# NRV-MEM-LCD.net
KiCad netlist of a schematic drawn in Altium Designer
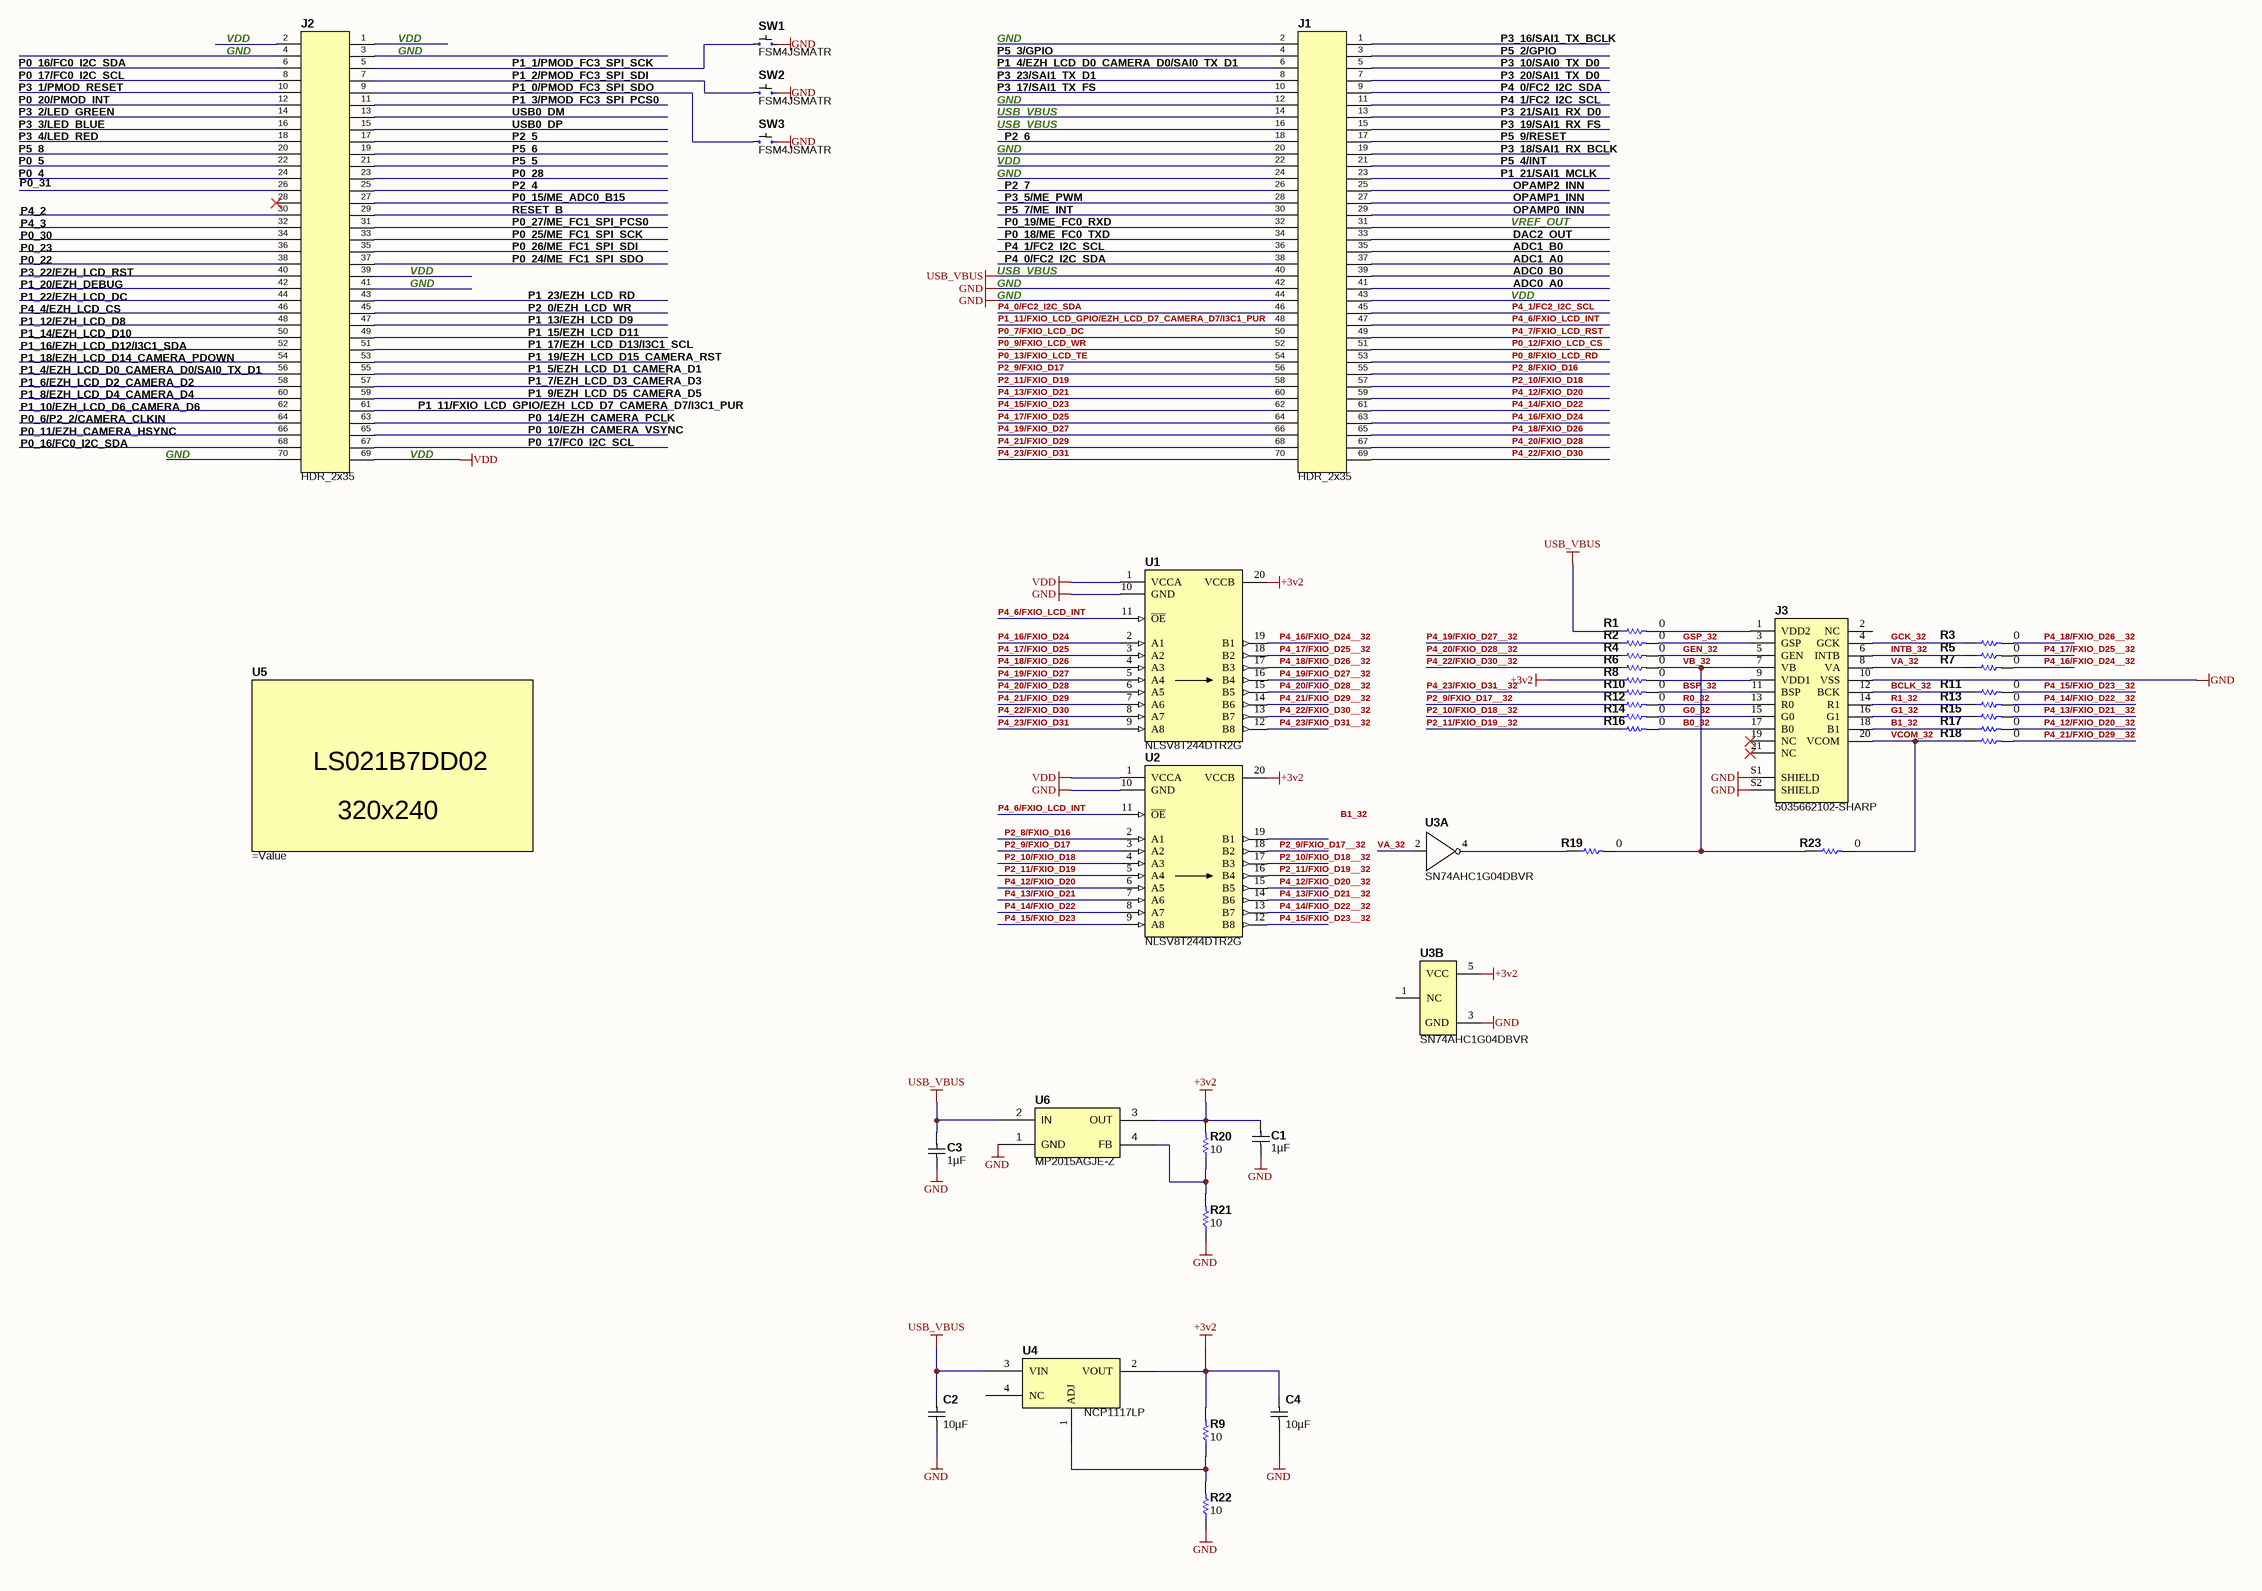
[diagram p0: NRV-MEM-LCD.SchDoc]

(export (version "E")
  (design (tool "Eeschema 10.0.6"))
  (components
    (comp (ref "C1")
      (value "1µF")
      (footprint "C0805_1.40MM_MD")
      (description "CAP CER 1UF 16V X7R 0805")
      (fields
        (field (name "MANUFACTURER PART NUMBER") "GCM21BR71C105KA58K")
        (field (name "MANUFACTURER") "Murata Electronics")
      )
      (libsource (lib "Capacitors - Murata - AEC-Q200") (part "C_2P_NP"))
    )
    (comp (ref "C2")
      (value "10µF")
      (footprint "C0805_1.40MM_MD")
      (description "CAP CER 10UF 10V X7R 0805")
      (fields
        (field (name "MANUFACTURER PART NUMBER") "GCM21BR71A106KE22K")
        (field (name "MANUFACTURER") "Murata Electronics")
      )
      (libsource (lib "Capacitors - Murata - AEC-Q200") (part "C_2P_NP"))
    )
    (comp (ref "C3")
      (value "1µF")
      (footprint "C0805_1.40MM_MD")
      (description "CAP CER 1UF 16V X7R 0805")
      (fields
        (field (name "MANUFACTURER PART NUMBER") "GCM21BR71C105KA58K")
        (field (name "MANUFACTURER") "Murata Electronics")
      )
      (libsource (lib "Capacitors - Murata - AEC-Q200") (part "C_2P_NP"))
    )
    (comp (ref "C4")
      (value "10µF")
      (footprint "C0805_1.40MM_MD")
      (description "CAP CER 10UF 10V X7R 0805")
      (fields
        (field (name "MANUFACTURER PART NUMBER") "GCM21BR71A106KE22K")
        (field (name "MANUFACTURER") "Murata Electronics")
      )
      (libsource (lib "Capacitors - Murata - AEC-Q200") (part "C_2P_NP"))
    )
    (comp (ref "J1")
      (value "HDR_2x35")
      (footprint "HEADER 2x35 .100\"")
      (description "2x35 Header .100\"")
      (libsource (lib "eConnector_Header") (part "HDR_2x35"))
    )
    (comp (ref "J2")
      (value "HDR_2x35")
      (footprint "HEADER 2x35 .100\"")
      (description "2x35 Header .100\"")
      (libsource (lib "eConnector_Header") (part "HDR_2x35"))
    )
    (comp (ref "J3")
      (value "5035662102-SHARP")
      (footprint "MOLEX_5035662102")
      (description "21 Position FPC Connector Contacts, Bottom 0.012 (0.30mm) Surface Mount, Right Angle")
      (fields (field (name "MANUFACTURER") "Molex") (field (name "MANUFACTURER PART NUMBER") "5035662102"))
      (libsource (lib "eConnector_FPC") (part "5035662102-SHARP"))
    )
    (comp (ref "R1")
      (value "0")
      (footprint "R0603_0.55MM_MD")
      (description "RES 0.0 OHM 1/10W JUMP 0603 SMD")
      (fields
        (field (name "MANUFACTURER PART NUMBER") "ERJ-3GEY0R00V")
        (field (name "MANUFACTURER") "Panasonic Electronic Components")
      )
      (libsource (lib "Resistors - Panasonic - AEC-Q200") (part "R_2P"))
    )
    (comp (ref "R2")
      (value "0")
      (footprint "R0603_0.55MM_MD")
      (description "RES 0.0 OHM 1/10W JUMP 0603 SMD")
      (fields
        (field (name "MANUFACTURER PART NUMBER") "ERJ-3GEY0R00V")
        (field (name "MANUFACTURER") "Panasonic Electronic Components")
      )
      (libsource (lib "Resistors - Panasonic - AEC-Q200") (part "R_2P"))
    )
    (comp (ref "R3")
      (value "0")
      (footprint "R0603_0.55MM_MD")
      (description "RES 0.0 OHM 1/10W JUMP 0603 SMD")
      (fields
        (field (name "MANUFACTURER PART NUMBER") "ERJ-3GEY0R00V")
        (field (name "MANUFACTURER") "Panasonic Electronic Components")
      )
      (libsource (lib "Resistors - Panasonic - AEC-Q200") (part "R_2P"))
    )
    (comp (ref "R4")
      (value "0")
      (footprint "R0603_0.55MM_MD")
      (description "RES 0.0 OHM 1/10W JUMP 0603 SMD")
      (fields
        (field (name "MANUFACTURER PART NUMBER") "ERJ-3GEY0R00V")
        (field (name "MANUFACTURER") "Panasonic Electronic Components")
      )
      (libsource (lib "Resistors - Panasonic - AEC-Q200") (part "R_2P"))
    )
    (comp (ref "R5")
      (value "0")
      (footprint "R0603_0.55MM_MD")
      (description "RES 0.0 OHM 1/10W JUMP 0603 SMD")
      (fields
        (field (name "MANUFACTURER PART NUMBER") "ERJ-3GEY0R00V")
        (field (name "MANUFACTURER") "Panasonic Electronic Components")
      )
      (libsource (lib "Resistors - Panasonic - AEC-Q200") (part "R_2P"))
    )
    (comp (ref "R6")
      (value "0")
      (footprint "R0603_0.55MM_MD")
      (description "RES 0.0 OHM 1/10W JUMP 0603 SMD")
      (fields
        (field (name "MANUFACTURER PART NUMBER") "ERJ-3GEY0R00V")
        (field (name "MANUFACTURER") "Panasonic Electronic Components")
      )
      (libsource (lib "Resistors - Panasonic - AEC-Q200") (part "R_2P"))
    )
    (comp (ref "R7")
      (value "0")
      (footprint "R0603_0.55MM_MD")
      (description "RES 0.0 OHM 1/10W JUMP 0603 SMD")
      (fields
        (field (name "MANUFACTURER PART NUMBER") "ERJ-3GEY0R00V")
        (field (name "MANUFACTURER") "Panasonic Electronic Components")
      )
      (libsource (lib "Resistors - Panasonic - AEC-Q200") (part "R_2P"))
    )
    (comp (ref "R8")
      (value "0")
      (footprint "R0603_0.55MM_MD")
      (description "RES 0.0 OHM 1/10W JUMP 0603 SMD")
      (fields
        (field (name "MANUFACTURER PART NUMBER") "ERJ-3GEY0R00V")
        (field (name "MANUFACTURER") "Panasonic Electronic Components")
      )
      (libsource (lib "Resistors - Panasonic - AEC-Q200") (part "R_2P"))
    )
    (comp (ref "R9")
      (value "10")
      (footprint "R0603_0.55MM_MD")
      (description "RES 10.0 OHM 1/10W 1% 0603 SMD")
      (libsource (lib "eResistors") (part "R"))
    )
    (comp (ref "R10")
      (value "0")
      (footprint "R0603_0.55MM_MD")
      (description "RES 0.0 OHM 1/10W JUMP 0603 SMD")
      (fields
        (field (name "MANUFACTURER PART NUMBER") "ERJ-3GEY0R00V")
        (field (name "MANUFACTURER") "Panasonic Electronic Components")
      )
      (libsource (lib "Resistors - Panasonic - AEC-Q200") (part "R_2P"))
    )
    (comp (ref "R11")
      (value "0")
      (footprint "R0603_0.55MM_MD")
      (description "RES 0.0 OHM 1/10W JUMP 0603 SMD")
      (fields
        (field (name "MANUFACTURER PART NUMBER") "ERJ-3GEY0R00V")
        (field (name "MANUFACTURER") "Panasonic Electronic Components")
      )
      (libsource (lib "Resistors - Panasonic - AEC-Q200") (part "R_2P"))
    )
    (comp (ref "R12")
      (value "0")
      (footprint "R0603_0.55MM_MD")
      (description "RES 0.0 OHM 1/10W JUMP 0603 SMD")
      (fields
        (field (name "MANUFACTURER PART NUMBER") "ERJ-3GEY0R00V")
        (field (name "MANUFACTURER") "Panasonic Electronic Components")
      )
      (libsource (lib "Resistors - Panasonic - AEC-Q200") (part "R_2P"))
    )
    (comp (ref "R13")
      (value "0")
      (footprint "R0603_0.55MM_MD")
      (description "RES 0.0 OHM 1/10W JUMP 0603 SMD")
      (fields
        (field (name "MANUFACTURER PART NUMBER") "ERJ-3GEY0R00V")
        (field (name "MANUFACTURER") "Panasonic Electronic Components")
      )
      (libsource (lib "Resistors - Panasonic - AEC-Q200") (part "R_2P"))
    )
    (comp (ref "R14")
      (value "0")
      (footprint "R0603_0.55MM_MD")
      (description "RES 0.0 OHM 1/10W JUMP 0603 SMD")
      (fields
        (field (name "MANUFACTURER PART NUMBER") "ERJ-3GEY0R00V")
        (field (name "MANUFACTURER") "Panasonic Electronic Components")
      )
      (libsource (lib "Resistors - Panasonic - AEC-Q200") (part "R_2P"))
    )
    (comp (ref "R15")
      (value "0")
      (footprint "R0603_0.55MM_MD")
      (description "RES 0.0 OHM 1/10W JUMP 0603 SMD")
      (fields
        (field (name "MANUFACTURER PART NUMBER") "ERJ-3GEY0R00V")
        (field (name "MANUFACTURER") "Panasonic Electronic Components")
      )
      (libsource (lib "Resistors - Panasonic - AEC-Q200") (part "R_2P"))
    )
    (comp (ref "R16")
      (value "0")
      (footprint "R0603_0.55MM_MD")
      (description "RES 0.0 OHM 1/10W JUMP 0603 SMD")
      (fields
        (field (name "MANUFACTURER PART NUMBER") "ERJ-3GEY0R00V")
        (field (name "MANUFACTURER") "Panasonic Electronic Components")
      )
      (libsource (lib "Resistors - Panasonic - AEC-Q200") (part "R_2P"))
    )
    (comp (ref "R17")
      (value "0")
      (footprint "R0603_0.55MM_MD")
      (description "RES 0.0 OHM 1/10W JUMP 0603 SMD")
      (fields
        (field (name "MANUFACTURER PART NUMBER") "ERJ-3GEY0R00V")
        (field (name "MANUFACTURER") "Panasonic Electronic Components")
      )
      (libsource (lib "Resistors - Panasonic - AEC-Q200") (part "R_2P"))
    )
    (comp (ref "R18")
      (value "0")
      (footprint "R0603_0.55MM_MD")
      (description "RES 0.0 OHM 1/10W JUMP 0603 SMD")
      (fields
        (field (name "MANUFACTURER PART NUMBER") "ERJ-3GEY0R00V")
        (field (name "MANUFACTURER") "Panasonic Electronic Components")
      )
      (libsource (lib "Resistors - Panasonic - AEC-Q200") (part "R_2P"))
    )
    (comp (ref "R19")
      (value "0")
      (footprint "R0603_0.55MM_MD")
      (description "RES 0.0 OHM 1/10W JUMP 0603 SMD")
      (fields
        (field (name "MANUFACTURER PART NUMBER") "ERJ-3GEY0R00V")
        (field (name "MANUFACTURER") "Panasonic Electronic Components")
      )
      (libsource (lib "Resistors - Panasonic - AEC-Q200") (part "R_2P"))
    )
    (comp (ref "R20")
      (value "10")
      (footprint "R0603_0.55MM_MD")
      (description "RES 10.0 OHM 1/10W 1% 0603 SMD")
      (libsource (lib "eResistors") (part "R"))
    )
    (comp (ref "R21")
      (value "10")
      (footprint "R0603_0.55MM_MD")
      (description "RES 10.0 OHM 1/10W 1% 0603 SMD")
      (libsource (lib "eResistors") (part "R"))
    )
    (comp (ref "R22")
      (value "10")
      (footprint "R0603_0.55MM_MD")
      (description "RES 10.0 OHM 1/10W 1% 0603 SMD")
      (libsource (lib "eResistors") (part "R"))
    )
    (comp (ref "R23")
      (value "0")
      (footprint "R0603_0.55MM_MD")
      (description "RES 0.0 OHM 1/10W JUMP 0603 SMD")
      (fields
        (field (name "MANUFACTURER PART NUMBER") "ERJ-3GEY0R00V")
        (field (name "MANUFACTURER") "Panasonic Electronic Components")
      )
      (libsource (lib "Resistors - Panasonic - AEC-Q200") (part "R_2P"))
    )
    (comp (ref "SW1")
      (value "FSM4JSMATR")
      (footprint "FSM4JSMA")
      (description "SWITCH TACTILE SPST-NO 0.05A 12V")
      (fields (field (name "MANUFACTURER") "TE Connectivity"))
      (libsource (lib "eElectroMechanical") (part "FSM4JSMATR"))
    )
    (comp (ref "SW2")
      (value "FSM4JSMATR")
      (footprint "FSM4JSMA")
      (description "SWITCH TACTILE SPST-NO 0.05A 12V")
      (fields (field (name "MANUFACTURER") "TE Connectivity"))
      (libsource (lib "eElectroMechanical") (part "FSM4JSMATR"))
    )
    (comp (ref "SW3")
      (value "FSM4JSMATR")
      (footprint "FSM4JSMA")
      (description "SWITCH TACTILE SPST-NO 0.05A 12V")
      (fields (field (name "MANUFACTURER") "TE Connectivity"))
      (libsource (lib "eElectroMechanical") (part "FSM4JSMATR"))
    )
    (comp (ref "U1")
      (value "NLSV8T244DTR2G")
      (footprint "TSOP65P640X105-20N")
      (description "NLSV8T244 Series 8 Bit 0.9 to 4.5 V Dual Non Inverting Level Translator-TSSOP-20")
      (libsource (lib "eIC") (part "NLSV8T244DTR2G"))
    )
    (comp (ref "U2")
      (value "NLSV8T244DTR2G")
      (footprint "TSOP65P640X105-20N")
      (description "NLSV8T244 Series 8 Bit 0.9 to 4.5 V Dual Non Inverting Level Translator-TSSOP-20")
      (libsource (lib "eIC") (part "NLSV8T244DTR2G"))
    )
    (comp (ref "U3")
      (value "SN74AHC1G04DBVR")
      (footprint "SOT95P245X145-5L")
      (description "IC SINGLE INVERTER GATE SOT23-5")
      (fields (field (name "MANUFACTURER") "Texas Instruments") (field (name "SOURCE") "Digikey"))
      (libsource (lib "eIC") (part "SN74AHC1G04DBVR"))
    )
    (comp (ref "U4")
      (value "NCP1117LP")
      (footprint "SOT223")
      (description "LDO Regulator Pos 1A 4-Pin(3+Tab) SOT-223 T/R / IC REG LDO ADJ 1A SOT223")
      (fields
        (field (name "MANUFACTURER") "ON Semiconductor")
        (field (name "MANUFACTURER PART NUMBER") "NCP1117LPSTADT3G")
      )
      (libsource (lib "eIC_Regulator") (part "NCP1117LP"))
    )
    (comp (ref "U5")
      (value "~")
      (footprint "LS021B7DD02")
      (description "LCD Display Module 5.4-in 240xRGBx320 45uW")
      (fields (field (name "MANUFACTURER") "Sharp") (field (name "MANUFACTURER PART NUMBER") "LS021B7DD02"))
      (libsource (lib "eModule") (part "LS021B7DD02"))
    )
    (comp (ref "U6")
      (value "MP2015AGJE-Z")
      (footprint "SOT23-4")
      (description "LDO Voltage Regulators 24V LowQuies Current Linear Regulator")
      (fields (field (name "MANUFACTURER") "Monolithic Power Systems"))
      (libsource (lib "eIC_Regulator") (part "MP2015AGJE-Z"))
    )
  )
  (nets
    (net (code "1") (name "+3v2") (class "Default")
      (node (ref "C1") (pin "2") (pinfunction "1_2") (pintype "passive"))
      (node (ref "C4") (pin "2") (pinfunction "1_2") (pintype "passive"))
      (node (ref "R20") (pin "2") (pinfunction "2_2") (pintype "passive"))
      (node (ref "R8") (pin "1") (pinfunction "1_1") (pintype "passive"))
      (node (ref "R9") (pin "2") (pinfunction "2_2") (pintype "passive"))
      (node (ref "U1") (pin "20") (pinfunction "VCCB_20") (pintype "power_in"))
      (node (ref "U2") (pin "20") (pinfunction "VCCB_20") (pintype "power_in"))
      (node (ref "U3") (pin "5") (pinfunction "VCC_5") (pintype "passive"))
      (node (ref "U4") (pin "2") (pinfunction "VOUT_2") (pintype "passive"))
      (node (ref "U6") (pin "3") (pinfunction "OUT_3") (pintype "passive"))
    )
    (net (code "2") (name "/B0_32") (class "Default")
      (node (ref "J3") (pin "17") (pinfunction "B0_17") (pintype "passive"))
      (node (ref "R16") (pin "2") (pinfunction "2_2") (pintype "passive"))
    )
    (net (code "3") (name "/B1_32") (class "Default")
      (node (ref "J3") (pin "18") (pinfunction "B1_18") (pintype "passive"))
      (node (ref "R17") (pin "1") (pinfunction "1_1") (pintype "passive"))
    )
    (net (code "4") (name "/BCLK_32") (class "Default")
      (node (ref "J3") (pin "12") (pinfunction "BCK_12") (pintype "passive"))
      (node (ref "R11") (pin "1") (pinfunction "1_1") (pintype "passive"))
    )
    (net (code "5") (name "/BSP_32") (class "Default")
      (node (ref "J3") (pin "11") (pinfunction "BSP_11") (pintype "passive"))
      (node (ref "R10") (pin "2") (pinfunction "2_2") (pintype "passive"))
    )
    (net (code "6") (name "/G0_32") (class "Default")
      (node (ref "J3") (pin "15") (pinfunction "G0_15") (pintype "passive"))
      (node (ref "R14") (pin "2") (pinfunction "2_2") (pintype "passive"))
    )
    (net (code "7") (name "/G1_32") (class "Default")
      (node (ref "J3") (pin "16") (pinfunction "G1_16") (pintype "passive"))
      (node (ref "R15") (pin "1") (pinfunction "1_1") (pintype "passive"))
    )
    (net (code "8") (name "/GCK_32") (class "Default")
      (node (ref "J3") (pin "4") (pinfunction "GCK_4") (pintype "passive"))
      (node (ref "R3") (pin "1") (pinfunction "1_1") (pintype "passive"))
    )
    (net (code "9") (name "/GEN_32") (class "Default")
      (node (ref "J3") (pin "5") (pinfunction "GEN_5") (pintype "passive"))
      (node (ref "R4") (pin "2") (pinfunction "2_2") (pintype "passive"))
    )
    (net (code "10") (name "/GSP_32") (class "Default")
      (node (ref "J3") (pin "3") (pinfunction "GSP_3") (pintype "passive"))
      (node (ref "R2") (pin "2") (pinfunction "2_2") (pintype "passive"))
    )
    (net (code "11") (name "/INTB_32") (class "Default")
      (node (ref "J3") (pin "6") (pinfunction "INTB_6") (pintype "passive"))
      (node (ref "R5") (pin "1") (pinfunction "1_1") (pintype "passive"))
    )
    (net (code "12") (name "/P0_7{slash}FXIO_LCD_DC") (class "Default")
      (node (ref "J1") (pin "50") (pinfunction "50_50") (pintype "passive"))
    )
    (net (code "13") (name "/P0_8{slash}FXIO_LCD_RD") (class "Default")
      (node (ref "J1") (pin "53") (pinfunction "53_53") (pintype "passive"))
    )
    (net (code "14") (name "/P0_9{slash}FXIO_LCD_WR") (class "Default")
      (node (ref "J1") (pin "52") (pinfunction "52_52") (pintype "passive"))
    )
    (net (code "15") (name "/P0_12{slash}FXIO_LCD_CS") (class "Default")
      (node (ref "J1") (pin "51") (pinfunction "51_51") (pintype "passive"))
    )
    (net (code "16") (name "/P0_13{slash}FXIO_LCD_TE") (class "Default")
      (node (ref "J1") (pin "54") (pinfunction "54_54") (pintype "passive"))
    )
    (net (code "17") (name "/P1_11{slash}FXIO_LCD_GPIO{slash}EZH_LCD_D7_CAMERA_D7{slash}I3C1_PUR") (class "Default")
      (node (ref "J1") (pin "48") (pinfunction "48_48") (pintype "passive"))
    )
    (net (code "18") (name "/P2_8{slash}FXIO_D16") (class "Default")
      (node (ref "J1") (pin "55") (pinfunction "55_55") (pintype "passive"))
      (node (ref "U2") (pin "2") (pinfunction "A1_2") (pintype "input"))
    )
    (net (code "19") (name "/P2_9{slash}FXIO_D17") (class "Default")
      (node (ref "J1") (pin "56") (pinfunction "56_56") (pintype "passive"))
      (node (ref "U2") (pin "3") (pinfunction "A2_3") (pintype "input"))
    )
    (net (code "20") (name "/P2_9{slash}FXIO_D17__32") (class "Default")
      (node (ref "R12") (pin "1") (pinfunction "1_1") (pintype "passive"))
      (node (ref "U2") (pin "18") (pinfunction "B2_18") (pintype "output"))
    )
    (net (code "21") (name "/P2_10{slash}FXIO_D18") (class "Default")
      (node (ref "J1") (pin "57") (pinfunction "57_57") (pintype "passive"))
      (node (ref "U2") (pin "4") (pinfunction "A3_4") (pintype "input"))
    )
    (net (code "22") (name "/P2_10{slash}FXIO_D18__32") (class "Default")
      (node (ref "R14") (pin "1") (pinfunction "1_1") (pintype "passive"))
      (node (ref "U2") (pin "17") (pinfunction "B3_17") (pintype "output"))
    )
    (net (code "23") (name "/P2_11{slash}FXIO_D19") (class "Default")
      (node (ref "J1") (pin "58") (pinfunction "58_58") (pintype "passive"))
      (node (ref "U2") (pin "5") (pinfunction "A4_5") (pintype "input"))
    )
    (net (code "24") (name "/P2_11{slash}FXIO_D19__32") (class "Default")
      (node (ref "R16") (pin "1") (pinfunction "1_1") (pintype "passive"))
      (node (ref "U2") (pin "16") (pinfunction "B4_16") (pintype "output"))
    )
    (net (code "25") (name "/P4_0{slash}FC2_I2C_SDA") (class "Default")
      (node (ref "J1") (pin "46") (pinfunction "46_46") (pintype "passive"))
    )
    (net (code "26") (name "/P4_1{slash}FC2_I2C_SCL") (class "Default")
      (node (ref "J1") (pin "45") (pinfunction "45_45") (pintype "passive"))
    )
    (net (code "27") (name "/P4_6{slash}FXIO_LCD_INT") (class "Default")
      (node (ref "J1") (pin "47") (pinfunction "47_47") (pintype "passive"))
      (node (ref "U1") (pin "11") (pinfunction "~{OE}_11") (pintype "input"))
      (node (ref "U2") (pin "11") (pinfunction "~{OE}_11") (pintype "input"))
    )
    (net (code "28") (name "/P4_7{slash}FXIO_LCD_RST") (class "Default")
      (node (ref "J1") (pin "49") (pinfunction "49_49") (pintype "passive"))
    )
    (net (code "29") (name "/P4_12{slash}FXIO_D20") (class "Default")
      (node (ref "J1") (pin "59") (pinfunction "59_59") (pintype "passive"))
      (node (ref "U2") (pin "6") (pinfunction "A5_6") (pintype "input"))
    )
    (net (code "30") (name "/P4_12{slash}FXIO_D20__32") (class "Default")
      (node (ref "R17") (pin "2") (pinfunction "2_2") (pintype "passive"))
      (node (ref "U2") (pin "15") (pinfunction "B5_15") (pintype "output"))
    )
    (net (code "31") (name "/P4_13{slash}FXIO_D21") (class "Default")
      (node (ref "J1") (pin "60") (pinfunction "60_60") (pintype "passive"))
      (node (ref "U2") (pin "7") (pinfunction "A6_7") (pintype "input"))
    )
    (net (code "32") (name "/P4_13{slash}FXIO_D21__32") (class "Default")
      (node (ref "R15") (pin "2") (pinfunction "2_2") (pintype "passive"))
      (node (ref "U2") (pin "14") (pinfunction "B6_14") (pintype "output"))
    )
    (net (code "33") (name "/P4_14{slash}FXIO_D22") (class "Default")
      (node (ref "J1") (pin "61") (pinfunction "61_61") (pintype "passive"))
      (node (ref "U2") (pin "8") (pinfunction "A7_8") (pintype "input"))
    )
    (net (code "34") (name "/P4_14{slash}FXIO_D22__32") (class "Default")
      (node (ref "R13") (pin "2") (pinfunction "2_2") (pintype "passive"))
      (node (ref "U2") (pin "13") (pinfunction "B7_13") (pintype "output"))
    )
    (net (code "35") (name "/P4_15{slash}FXIO_D23") (class "Default")
      (node (ref "J1") (pin "62") (pinfunction "62_62") (pintype "passive"))
      (node (ref "U2") (pin "9") (pinfunction "A8_9") (pintype "input"))
    )
    (net (code "36") (name "/P4_15{slash}FXIO_D23__32") (class "Default")
      (node (ref "R11") (pin "2") (pinfunction "2_2") (pintype "passive"))
      (node (ref "U2") (pin "12") (pinfunction "B8_12") (pintype "output"))
    )
    (net (code "37") (name "/P4_16{slash}FXIO_D24") (class "Default")
      (node (ref "J1") (pin "63") (pinfunction "63_63") (pintype "passive"))
      (node (ref "U1") (pin "2") (pinfunction "A1_2") (pintype "input"))
    )
    (net (code "38") (name "/P4_16{slash}FXIO_D24__32") (class "Default")
      (node (ref "R7") (pin "2") (pinfunction "2_2") (pintype "passive"))
      (node (ref "U1") (pin "19") (pinfunction "B1_19") (pintype "output"))
    )
    (net (code "39") (name "/P4_17{slash}FXIO_D25") (class "Default")
      (node (ref "J1") (pin "64") (pinfunction "64_64") (pintype "passive"))
      (node (ref "U1") (pin "3") (pinfunction "A2_3") (pintype "input"))
    )
    (net (code "40") (name "/P4_17{slash}FXIO_D25__32") (class "Default")
      (node (ref "R5") (pin "2") (pinfunction "2_2") (pintype "passive"))
      (node (ref "U1") (pin "18") (pinfunction "B2_18") (pintype "output"))
    )
    (net (code "41") (name "/P4_18{slash}FXIO_D26") (class "Default")
      (node (ref "J1") (pin "65") (pinfunction "65_65") (pintype "passive"))
      (node (ref "U1") (pin "4") (pinfunction "A3_4") (pintype "input"))
    )
    (net (code "42") (name "/P4_18{slash}FXIO_D26__32") (class "Default")
      (node (ref "R3") (pin "2") (pinfunction "2_2") (pintype "passive"))
      (node (ref "U1") (pin "17") (pinfunction "B3_17") (pintype "output"))
    )
    (net (code "43") (name "/P4_19{slash}FXIO_D27") (class "Default")
      (node (ref "J1") (pin "66") (pinfunction "66_66") (pintype "passive"))
      (node (ref "U1") (pin "5") (pinfunction "A4_5") (pintype "input"))
    )
    (net (code "44") (name "/P4_19{slash}FXIO_D27__32") (class "Default")
      (node (ref "R2") (pin "1") (pinfunction "1_1") (pintype "passive"))
      (node (ref "U1") (pin "16") (pinfunction "B4_16") (pintype "output"))
    )
    (net (code "45") (name "/P4_20{slash}FXIO_D28") (class "Default")
      (node (ref "J1") (pin "67") (pinfunction "67_67") (pintype "passive"))
      (node (ref "U1") (pin "6") (pinfunction "A5_6") (pintype "input"))
    )
    (net (code "46") (name "/P4_20{slash}FXIO_D28__32") (class "Default")
      (node (ref "R4") (pin "1") (pinfunction "1_1") (pintype "passive"))
      (node (ref "U1") (pin "15") (pinfunction "B5_15") (pintype "output"))
    )
    (net (code "47") (name "/P4_21{slash}FXIO_D29") (class "Default")
      (node (ref "J1") (pin "68") (pinfunction "68_68") (pintype "passive"))
      (node (ref "U1") (pin "7") (pinfunction "A6_7") (pintype "input"))
    )
    (net (code "48") (name "/P4_21{slash}FXIO_D29__32") (class "Default")
      (node (ref "R18") (pin "2") (pinfunction "2_2") (pintype "passive"))
      (node (ref "U1") (pin "14") (pinfunction "B6_14") (pintype "output"))
    )
    (net (code "49") (name "/P4_22{slash}FXIO_D30") (class "Default")
      (node (ref "J1") (pin "69") (pinfunction "69_69") (pintype "passive"))
      (node (ref "U1") (pin "8") (pinfunction "A7_8") (pintype "input"))
    )
    (net (code "50") (name "/P4_22{slash}FXIO_D30__32") (class "Default")
      (node (ref "R6") (pin "1") (pinfunction "1_1") (pintype "passive"))
      (node (ref "U1") (pin "13") (pinfunction "B7_13") (pintype "output"))
    )
    (net (code "51") (name "/P4_23{slash}FXIO_D31") (class "Default")
      (node (ref "J1") (pin "70") (pinfunction "70_70") (pintype "passive"))
      (node (ref "U1") (pin "9") (pinfunction "A8_9") (pintype "input"))
    )
    (net (code "52") (name "/P4_23{slash}FXIO_D31__32") (class "Default")
      (node (ref "R10") (pin "1") (pinfunction "1_1") (pintype "passive"))
      (node (ref "U1") (pin "12") (pinfunction "B8_12") (pintype "output"))
    )
    (net (code "53") (name "/R0_32") (class "Default")
      (node (ref "J3") (pin "13") (pinfunction "R0_13") (pintype "passive"))
      (node (ref "R12") (pin "2") (pinfunction "2_2") (pintype "passive"))
    )
    (net (code "54") (name "/R1_32") (class "Default")
      (node (ref "J3") (pin "14") (pinfunction "R1_14") (pintype "passive"))
      (node (ref "R13") (pin "1") (pinfunction "1_1") (pintype "passive"))
    )
    (net (code "55") (name "/VA_32") (class "Default")
      (node (ref "J3") (pin "8") (pinfunction "VA_8") (pintype "passive"))
      (node (ref "R7") (pin "1") (pinfunction "1_1") (pintype "passive"))
      (node (ref "U3") (pin "2") (pinfunction "A_2") (pintype "passive"))
    )
    (net (code "56") (name "/VB_32") (class "Default")
      (node (ref "J3") (pin "7") (pinfunction "VB_7") (pintype "passive"))
      (node (ref "R19") (pin "2") (pinfunction "2_2") (pintype "passive"))
      (node (ref "R23") (pin "1") (pinfunction "1_1") (pintype "passive"))
      (node (ref "R6") (pin "2") (pinfunction "2_2") (pintype "passive"))
    )
    (net (code "57") (name "/VCOM_32") (class "Default")
      (node (ref "J3") (pin "20") (pinfunction "VCOM_20") (pintype "passive"))
      (node (ref "R18") (pin "1") (pinfunction "1_1") (pintype "passive"))
      (node (ref "R23") (pin "2") (pinfunction "2_2") (pintype "passive"))
    )
    (net (code "58") (name "GND") (class "Default")
      (node (ref "C1") (pin "1") (pinfunction "1_1") (pintype "passive"))
      (node (ref "C2") (pin "1") (pinfunction "1_1") (pintype "passive"))
      (node (ref "C3") (pin "1") (pinfunction "1_1") (pintype "passive"))
      (node (ref "C4") (pin "1") (pinfunction "1_1") (pintype "passive"))
      (node (ref "J1") (pin "42") (pinfunction "42_42") (pintype "passive"))
      (node (ref "J1") (pin "44") (pinfunction "44_44") (pintype "passive"))
      (node (ref "J3") (pin "10") (pinfunction "VSS_10") (pintype "passive"))
      (node (ref "J3") (pin "S1") (pinfunction "SHIELD_S1") (pintype "passive"))
      (node (ref "J3") (pin "S2") (pinfunction "SHIELD_S2") (pintype "passive"))
      (node (ref "R21") (pin "1") (pinfunction "1_1") (pintype "passive"))
      (node (ref "R22") (pin "1") (pinfunction "1_1") (pintype "passive"))
      (node (ref "SW1") (pin "A") (pinfunction "A_A") (pintype "passive"))
      (node (ref "SW2") (pin "A") (pinfunction "A_A") (pintype "passive"))
      (node (ref "SW3") (pin "A") (pinfunction "A_A") (pintype "passive"))
      (node (ref "U1") (pin "10") (pinfunction "GND_10") (pintype "power_in"))
      (node (ref "U2") (pin "10") (pinfunction "GND_10") (pintype "power_in"))
      (node (ref "U3") (pin "3") (pinfunction "GND_3") (pintype "passive"))
      (node (ref "U6") (pin "1") (pinfunction "GND_1") (pintype "passive"))
    )
    (net (code "59") (name "Net-(J2-Pad5)") (class "Default")
      (node (ref "J2") (pin "5") (pinfunction "5_5") (pintype "passive"))
      (node (ref "SW1") (pin "B") (pinfunction "B_B") (pintype "passive"))
    )
    (net (code "60") (name "Net-(J2-Pad7)") (class "Default")
      (node (ref "J2") (pin "7") (pinfunction "7_7") (pintype "passive"))
      (node (ref "SW2") (pin "B") (pinfunction "B_B") (pintype "passive"))
    )
    (net (code "61") (name "Net-(J2-Pad9)") (class "Default")
      (node (ref "J2") (pin "9") (pinfunction "9_9") (pintype "passive"))
      (node (ref "SW3") (pin "B") (pinfunction "B_B") (pintype "passive"))
    )
    (net (code "62") (name "Net-(J3-VDD1)") (class "Default")
      (node (ref "J3") (pin "9") (pinfunction "VDD1_9") (pintype "passive"))
      (node (ref "R8") (pin "2") (pinfunction "2_2") (pintype "passive"))
    )
    (net (code "63") (name "Net-(J3-VDD2)") (class "Default")
      (node (ref "J3") (pin "1") (pinfunction "VDD2_1") (pintype "passive"))
      (node (ref "R1") (pin "2") (pinfunction "2_2") (pintype "passive"))
    )
    (net (code "64") (name "Net-(U3A-OUT)") (class "Default")
      (node (ref "R19") (pin "1") (pinfunction "1_1") (pintype "passive"))
      (node (ref "U3") (pin "4") (pinfunction "OUT_4") (pintype "passive"))
    )
    (net (code "65") (name "Net-(U4-ADJ)") (class "Default")
      (node (ref "R22") (pin "2") (pinfunction "2_2") (pintype "passive"))
      (node (ref "R9") (pin "1") (pinfunction "1_1") (pintype "passive"))
      (node (ref "U4") (pin "1") (pinfunction "ADJ_1") (pintype "passive"))
    )
    (net (code "66") (name "Net-(U6-FB)") (class "Default")
      (node (ref "R20") (pin "1") (pinfunction "1_1") (pintype "passive"))
      (node (ref "R21") (pin "2") (pinfunction "2_2") (pintype "passive"))
      (node (ref "U6") (pin "4") (pinfunction "FB_4") (pintype "passive"))
    )
    (net (code "67") (name "USB_VBUS") (class "Default")
      (node (ref "C2") (pin "2") (pinfunction "1_2") (pintype "passive"))
      (node (ref "C3") (pin "2") (pinfunction "1_2") (pintype "passive"))
      (node (ref "J1") (pin "40") (pinfunction "40_40") (pintype "passive"))
      (node (ref "R1") (pin "1") (pinfunction "1_1") (pintype "passive"))
      (node (ref "U4") (pin "3") (pinfunction "VIN_3") (pintype "passive"))
      (node (ref "U6") (pin "2") (pinfunction "IN_2") (pintype "passive"))
    )
    (net (code "68") (name "VDD") (class "Default")
      (node (ref "J2") (pin "69") (pinfunction "69_69") (pintype "passive"))
      (node (ref "U1") (pin "1") (pinfunction "VCCA_1") (pintype "power_in"))
      (node (ref "U2") (pin "1") (pinfunction "VCCA_1") (pintype "power_in"))
    )
    (net (code "69") (name "unconnected-(J1-Pad1)") (class "Default")
      (node (ref "J1") (pin "1") (pinfunction "1_1") (pintype "passive"))
    )
    (net (code "70") (name "unconnected-(J1-Pad2)") (class "Default")
      (node (ref "J1") (pin "2") (pinfunction "2_2") (pintype "passive"))
    )
    (net (code "71") (name "unconnected-(J1-Pad3)") (class "Default")
      (node (ref "J1") (pin "3") (pinfunction "3_3") (pintype "passive"))
    )
    (net (code "72") (name "unconnected-(J1-Pad4)") (class "Default")
      (node (ref "J1") (pin "4") (pinfunction "4_4") (pintype "passive"))
    )
    (net (code "73") (name "unconnected-(J1-Pad5)") (class "Default")
      (node (ref "J1") (pin "5") (pinfunction "5_5") (pintype "passive"))
    )
    (net (code "74") (name "unconnected-(J1-Pad6)") (class "Default")
      (node (ref "J1") (pin "6") (pinfunction "6_6") (pintype "passive"))
    )
    (net (code "75") (name "unconnected-(J1-Pad7)") (class "Default")
      (node (ref "J1") (pin "7") (pinfunction "7_7") (pintype "passive"))
    )
    (net (code "76") (name "unconnected-(J1-Pad8)") (class "Default")
      (node (ref "J1") (pin "8") (pinfunction "8_8") (pintype "passive"))
    )
    (net (code "77") (name "unconnected-(J1-Pad9)") (class "Default")
      (node (ref "J1") (pin "9") (pinfunction "9_9") (pintype "passive"))
    )
    (net (code "78") (name "unconnected-(J1-Pad10)") (class "Default")
      (node (ref "J1") (pin "10") (pinfunction "10_10") (pintype "passive"))
    )
    (net (code "79") (name "unconnected-(J1-Pad11)") (class "Default")
      (node (ref "J1") (pin "11") (pinfunction "11_11") (pintype "passive"))
    )
    (net (code "80") (name "unconnected-(J1-Pad12)") (class "Default")
      (node (ref "J1") (pin "12") (pinfunction "12_12") (pintype "passive"))
    )
    (net (code "81") (name "unconnected-(J1-Pad13)") (class "Default")
      (node (ref "J1") (pin "13") (pinfunction "13_13") (pintype "passive"))
    )
    (net (code "82") (name "unconnected-(J1-Pad14)") (class "Default")
      (node (ref "J1") (pin "14") (pinfunction "14_14") (pintype "passive"))
    )
    (net (code "83") (name "unconnected-(J1-Pad15)") (class "Default")
      (node (ref "J1") (pin "15") (pinfunction "15_15") (pintype "passive"))
    )
    (net (code "84") (name "unconnected-(J1-Pad16)") (class "Default")
      (node (ref "J1") (pin "16") (pinfunction "16_16") (pintype "passive"))
    )
    (net (code "85") (name "unconnected-(J1-Pad17)") (class "Default")
      (node (ref "J1") (pin "17") (pinfunction "17_17") (pintype "passive"))
    )
    (net (code "86") (name "unconnected-(J1-Pad18)") (class "Default")
      (node (ref "J1") (pin "18") (pinfunction "18_18") (pintype "passive"))
    )
    (net (code "87") (name "unconnected-(J1-Pad19)") (class "Default")
      (node (ref "J1") (pin "19") (pinfunction "19_19") (pintype "passive"))
    )
    (net (code "88") (name "unconnected-(J1-Pad20)") (class "Default")
      (node (ref "J1") (pin "20") (pinfunction "20_20") (pintype "passive"))
    )
    (net (code "89") (name "unconnected-(J1-Pad21)") (class "Default")
      (node (ref "J1") (pin "21") (pinfunction "21_21") (pintype "passive"))
    )
    (net (code "90") (name "unconnected-(J1-Pad22)") (class "Default")
      (node (ref "J1") (pin "22") (pinfunction "22_22") (pintype "passive"))
    )
    (net (code "91") (name "unconnected-(J1-Pad23)") (class "Default")
      (node (ref "J1") (pin "23") (pinfunction "23_23") (pintype "passive"))
    )
    (net (code "92") (name "unconnected-(J1-Pad24)") (class "Default")
      (node (ref "J1") (pin "24") (pinfunction "24_24") (pintype "passive"))
    )
    (net (code "93") (name "unconnected-(J1-Pad25)") (class "Default")
      (node (ref "J1") (pin "25") (pinfunction "25_25") (pintype "passive"))
    )
    (net (code "94") (name "unconnected-(J1-Pad26)") (class "Default")
      (node (ref "J1") (pin "26") (pinfunction "26_26") (pintype "passive"))
    )
    (net (code "95") (name "unconnected-(J1-Pad27)") (class "Default")
      (node (ref "J1") (pin "27") (pinfunction "27_27") (pintype "passive"))
    )
    (net (code "96") (name "unconnected-(J1-Pad28)") (class "Default")
      (node (ref "J1") (pin "28") (pinfunction "28_28") (pintype "passive"))
    )
    (net (code "97") (name "unconnected-(J1-Pad29)") (class "Default")
      (node (ref "J1") (pin "29") (pinfunction "29_29") (pintype "passive"))
    )
    (net (code "98") (name "unconnected-(J1-Pad30)") (class "Default")
      (node (ref "J1") (pin "30") (pinfunction "30_30") (pintype "passive"))
    )
    (net (code "99") (name "unconnected-(J1-Pad31)") (class "Default")
      (node (ref "J1") (pin "31") (pinfunction "31_31") (pintype "passive"))
    )
    (net (code "100") (name "unconnected-(J1-Pad32)") (class "Default")
      (node (ref "J1") (pin "32") (pinfunction "32_32") (pintype "passive"))
    )
    (net (code "101") (name "unconnected-(J1-Pad33)") (class "Default")
      (node (ref "J1") (pin "33") (pinfunction "33_33") (pintype "passive"))
    )
    (net (code "102") (name "unconnected-(J1-Pad34)") (class "Default")
      (node (ref "J1") (pin "34") (pinfunction "34_34") (pintype "passive"))
    )
    (net (code "103") (name "unconnected-(J1-Pad35)") (class "Default")
      (node (ref "J1") (pin "35") (pinfunction "35_35") (pintype "passive"))
    )
    (net (code "104") (name "unconnected-(J1-Pad36)") (class "Default")
      (node (ref "J1") (pin "36") (pinfunction "36_36") (pintype "passive"))
    )
    (net (code "105") (name "unconnected-(J1-Pad37)") (class "Default")
      (node (ref "J1") (pin "37") (pinfunction "37_37") (pintype "passive"))
    )
    (net (code "106") (name "unconnected-(J1-Pad38)") (class "Default")
      (node (ref "J1") (pin "38") (pinfunction "38_38") (pintype "passive"))
    )
    (net (code "107") (name "unconnected-(J1-Pad39)") (class "Default")
      (node (ref "J1") (pin "39") (pinfunction "39_39") (pintype "passive"))
    )
    (net (code "108") (name "unconnected-(J1-Pad41)") (class "Default")
      (node (ref "J1") (pin "41") (pinfunction "41_41") (pintype "passive"))
    )
    (net (code "109") (name "unconnected-(J1-Pad43)") (class "Default")
      (node (ref "J1") (pin "43") (pinfunction "43_43") (pintype "passive"))
    )
    (net (code "110") (name "unconnected-(J2-Pad1)") (class "Default")
      (node (ref "J2") (pin "1") (pinfunction "1_1") (pintype "passive"))
    )
    (net (code "111") (name "unconnected-(J2-Pad2)") (class "Default")
      (node (ref "J2") (pin "2") (pinfunction "2_2") (pintype "passive"))
    )
    (net (code "112") (name "unconnected-(J2-Pad3)") (class "Default")
      (node (ref "J2") (pin "3") (pinfunction "3_3") (pintype "passive"))
    )
    (net (code "113") (name "unconnected-(J2-Pad4)") (class "Default")
      (node (ref "J2") (pin "4") (pinfunction "4_4") (pintype "passive"))
    )
    (net (code "114") (name "unconnected-(J2-Pad6)") (class "Default")
      (node (ref "J2") (pin "6") (pinfunction "6_6") (pintype "passive"))
    )
    (net (code "115") (name "unconnected-(J2-Pad8)") (class "Default")
      (node (ref "J2") (pin "8") (pinfunction "8_8") (pintype "passive"))
    )
    (net (code "116") (name "unconnected-(J2-Pad10)") (class "Default")
      (node (ref "J2") (pin "10") (pinfunction "10_10") (pintype "passive"))
    )
    (net (code "117") (name "unconnected-(J2-Pad11)") (class "Default")
      (node (ref "J2") (pin "11") (pinfunction "11_11") (pintype "passive"))
    )
    (net (code "118") (name "unconnected-(J2-Pad12)") (class "Default")
      (node (ref "J2") (pin "12") (pinfunction "12_12") (pintype "passive"))
    )
    (net (code "119") (name "unconnected-(J2-Pad13)") (class "Default")
      (node (ref "J2") (pin "13") (pinfunction "13_13") (pintype "passive"))
    )
    (net (code "120") (name "unconnected-(J2-Pad14)") (class "Default")
      (node (ref "J2") (pin "14") (pinfunction "14_14") (pintype "passive"))
    )
    (net (code "121") (name "unconnected-(J2-Pad15)") (class "Default")
      (node (ref "J2") (pin "15") (pinfunction "15_15") (pintype "passive"))
    )
    (net (code "122") (name "unconnected-(J2-Pad16)") (class "Default")
      (node (ref "J2") (pin "16") (pinfunction "16_16") (pintype "passive"))
    )
    (net (code "123") (name "unconnected-(J2-Pad17)") (class "Default")
      (node (ref "J2") (pin "17") (pinfunction "17_17") (pintype "passive"))
    )
    (net (code "124") (name "unconnected-(J2-Pad18)") (class "Default")
      (node (ref "J2") (pin "18") (pinfunction "18_18") (pintype "passive"))
    )
    (net (code "125") (name "unconnected-(J2-Pad19)") (class "Default")
      (node (ref "J2") (pin "19") (pinfunction "19_19") (pintype "passive"))
    )
    (net (code "126") (name "unconnected-(J2-Pad20)") (class "Default")
      (node (ref "J2") (pin "20") (pinfunction "20_20") (pintype "passive"))
    )
    (net (code "127") (name "unconnected-(J2-Pad21)") (class "Default")
      (node (ref "J2") (pin "21") (pinfunction "21_21") (pintype "passive"))
    )
    (net (code "128") (name "unconnected-(J2-Pad22)") (class "Default")
      (node (ref "J2") (pin "22") (pinfunction "22_22") (pintype "passive"))
    )
    (net (code "129") (name "unconnected-(J2-Pad23)") (class "Default")
      (node (ref "J2") (pin "23") (pinfunction "23_23") (pintype "passive"))
    )
    (net (code "130") (name "unconnected-(J2-Pad24)") (class "Default")
      (node (ref "J2") (pin "24") (pinfunction "24_24") (pintype "passive"))
    )
    (net (code "131") (name "unconnected-(J2-Pad25)") (class "Default")
      (node (ref "J2") (pin "25") (pinfunction "25_25") (pintype "passive"))
    )
    (net (code "132") (name "unconnected-(J2-Pad26)") (class "Default")
      (node (ref "J2") (pin "26") (pinfunction "26_26") (pintype "passive"))
    )
    (net (code "133") (name "unconnected-(J2-Pad27)") (class "Default")
      (node (ref "J2") (pin "27") (pinfunction "27_27") (pintype "passive"))
    )
    (net (code "134") (name "unconnected-(J2-Pad28)") (class "Default")
      (node (ref "J2") (pin "28") (pinfunction "28_28") (pintype "passive+no_connect"))
    )
    (net (code "135") (name "unconnected-(J2-Pad29)") (class "Default")
      (node (ref "J2") (pin "29") (pinfunction "29_29") (pintype "passive"))
    )
    (net (code "136") (name "unconnected-(J2-Pad30)") (class "Default")
      (node (ref "J2") (pin "30") (pinfunction "30_30") (pintype "passive"))
    )
    (net (code "137") (name "unconnected-(J2-Pad31)") (class "Default")
      (node (ref "J2") (pin "31") (pinfunction "31_31") (pintype "passive"))
    )
    (net (code "138") (name "unconnected-(J2-Pad32)") (class "Default")
      (node (ref "J2") (pin "32") (pinfunction "32_32") (pintype "passive"))
    )
    (net (code "139") (name "unconnected-(J2-Pad33)") (class "Default")
      (node (ref "J2") (pin "33") (pinfunction "33_33") (pintype "passive"))
    )
    (net (code "140") (name "unconnected-(J2-Pad34)") (class "Default")
      (node (ref "J2") (pin "34") (pinfunction "34_34") (pintype "passive"))
    )
    (net (code "141") (name "unconnected-(J2-Pad35)") (class "Default")
      (node (ref "J2") (pin "35") (pinfunction "35_35") (pintype "passive"))
    )
    (net (code "142") (name "unconnected-(J2-Pad36)") (class "Default")
      (node (ref "J2") (pin "36") (pinfunction "36_36") (pintype "passive"))
    )
    (net (code "143") (name "unconnected-(J2-Pad37)") (class "Default")
      (node (ref "J2") (pin "37") (pinfunction "37_37") (pintype "passive"))
    )
    (net (code "144") (name "unconnected-(J2-Pad38)") (class "Default")
      (node (ref "J2") (pin "38") (pinfunction "38_38") (pintype "passive"))
    )
    (net (code "145") (name "unconnected-(J2-Pad39)") (class "Default")
      (node (ref "J2") (pin "39") (pinfunction "39_39") (pintype "passive"))
    )
    (net (code "146") (name "unconnected-(J2-Pad40)") (class "Default")
      (node (ref "J2") (pin "40") (pinfunction "40_40") (pintype "passive"))
    )
    (net (code "147") (name "unconnected-(J2-Pad41)") (class "Default")
      (node (ref "J2") (pin "41") (pinfunction "41_41") (pintype "passive"))
    )
    (net (code "148") (name "unconnected-(J2-Pad42)") (class "Default")
      (node (ref "J2") (pin "42") (pinfunction "42_42") (pintype "passive"))
    )
    (net (code "149") (name "unconnected-(J2-Pad43)") (class "Default")
      (node (ref "J2") (pin "43") (pinfunction "43_43") (pintype "passive"))
    )
    (net (code "150") (name "unconnected-(J2-Pad44)") (class "Default")
      (node (ref "J2") (pin "44") (pinfunction "44_44") (pintype "passive"))
    )
    (net (code "151") (name "unconnected-(J2-Pad45)") (class "Default")
      (node (ref "J2") (pin "45") (pinfunction "45_45") (pintype "passive"))
    )
    (net (code "152") (name "unconnected-(J2-Pad46)") (class "Default")
      (node (ref "J2") (pin "46") (pinfunction "46_46") (pintype "passive"))
    )
    (net (code "153") (name "unconnected-(J2-Pad47)") (class "Default")
      (node (ref "J2") (pin "47") (pinfunction "47_47") (pintype "passive"))
    )
    (net (code "154") (name "unconnected-(J2-Pad48)") (class "Default")
      (node (ref "J2") (pin "48") (pinfunction "48_48") (pintype "passive"))
    )
    (net (code "155") (name "unconnected-(J2-Pad49)") (class "Default")
      (node (ref "J2") (pin "49") (pinfunction "49_49") (pintype "passive"))
    )
    (net (code "156") (name "unconnected-(J2-Pad50)") (class "Default")
      (node (ref "J2") (pin "50") (pinfunction "50_50") (pintype "passive"))
    )
    (net (code "157") (name "unconnected-(J2-Pad51)") (class "Default")
      (node (ref "J2") (pin "51") (pinfunction "51_51") (pintype "passive"))
    )
    (net (code "158") (name "unconnected-(J2-Pad52)") (class "Default")
      (node (ref "J2") (pin "52") (pinfunction "52_52") (pintype "passive"))
    )
    (net (code "159") (name "unconnected-(J2-Pad53)") (class "Default")
      (node (ref "J2") (pin "53") (pinfunction "53_53") (pintype "passive"))
    )
    (net (code "160") (name "unconnected-(J2-Pad54)") (class "Default")
      (node (ref "J2") (pin "54") (pinfunction "54_54") (pintype "passive"))
    )
    (net (code "161") (name "unconnected-(J2-Pad55)") (class "Default")
      (node (ref "J2") (pin "55") (pinfunction "55_55") (pintype "passive"))
    )
    (net (code "162") (name "unconnected-(J2-Pad56)") (class "Default")
      (node (ref "J2") (pin "56") (pinfunction "56_56") (pintype "passive"))
    )
    (net (code "163") (name "unconnected-(J2-Pad57)") (class "Default")
      (node (ref "J2") (pin "57") (pinfunction "57_57") (pintype "passive"))
    )
    (net (code "164") (name "unconnected-(J2-Pad58)") (class "Default")
      (node (ref "J2") (pin "58") (pinfunction "58_58") (pintype "passive"))
    )
    (net (code "165") (name "unconnected-(J2-Pad59)") (class "Default")
      (node (ref "J2") (pin "59") (pinfunction "59_59") (pintype "passive"))
    )
    (net (code "166") (name "unconnected-(J2-Pad60)") (class "Default")
      (node (ref "J2") (pin "60") (pinfunction "60_60") (pintype "passive"))
    )
    (net (code "167") (name "unconnected-(J2-Pad61)") (class "Default")
      (node (ref "J2") (pin "61") (pinfunction "61_61") (pintype "passive"))
    )
    (net (code "168") (name "unconnected-(J2-Pad62)") (class "Default")
      (node (ref "J2") (pin "62") (pinfunction "62_62") (pintype "passive"))
    )
    (net (code "169") (name "unconnected-(J2-Pad63)") (class "Default")
      (node (ref "J2") (pin "63") (pinfunction "63_63") (pintype "passive"))
    )
    (net (code "170") (name "unconnected-(J2-Pad64)") (class "Default")
      (node (ref "J2") (pin "64") (pinfunction "64_64") (pintype "passive"))
    )
    (net (code "171") (name "unconnected-(J2-Pad65)") (class "Default")
      (node (ref "J2") (pin "65") (pinfunction "65_65") (pintype "passive"))
    )
    (net (code "172") (name "unconnected-(J2-Pad66)") (class "Default")
      (node (ref "J2") (pin "66") (pinfunction "66_66") (pintype "passive"))
    )
    (net (code "173") (name "unconnected-(J2-Pad67)") (class "Default")
      (node (ref "J2") (pin "67") (pinfunction "67_67") (pintype "passive"))
    )
    (net (code "174") (name "unconnected-(J2-Pad68)") (class "Default")
      (node (ref "J2") (pin "68") (pinfunction "68_68") (pintype "passive"))
    )
    (net (code "175") (name "unconnected-(J2-Pad70)") (class "Default")
      (node (ref "J2") (pin "70") (pinfunction "70_70") (pintype "passive"))
    )
    (net (code "176") (name "unconnected-(J3-NC-Pad2)") (class "Default")
      (node (ref "J3") (pin "2") (pinfunction "NC_2") (pintype "passive"))
    )
    (net (code "177") (name "unconnected-(J3-NC-Pad19)") (class "Default")
      (node (ref "J3") (pin "19") (pinfunction "NC_19") (pintype "passive+no_connect"))
    )
    (net (code "178") (name "unconnected-(J3-NC-Pad21)") (class "Default")
      (node (ref "J3") (pin "21") (pinfunction "NC_21") (pintype "passive+no_connect"))
    )
    (net (code "179") (name "unconnected-(U2-B1-Pad19)") (class "Default")
      (node (ref "U2") (pin "19") (pinfunction "B1_19") (pintype "output"))
    )
    (net (code "180") (name "unconnected-(U3B-NC-Pad1)") (class "Default")
      (node (ref "U3") (pin "1") (pinfunction "NC_1") (pintype "passive"))
    )
    (net (code "181") (name "unconnected-(U4-NC-Pad4)") (class "Default")
      (node (ref "U4") (pin "4") (pinfunction "NC_4") (pintype "passive"))
    )
  )
)
